# APPS.net
KiCad netlist of a schematic drawn in Altium Designer
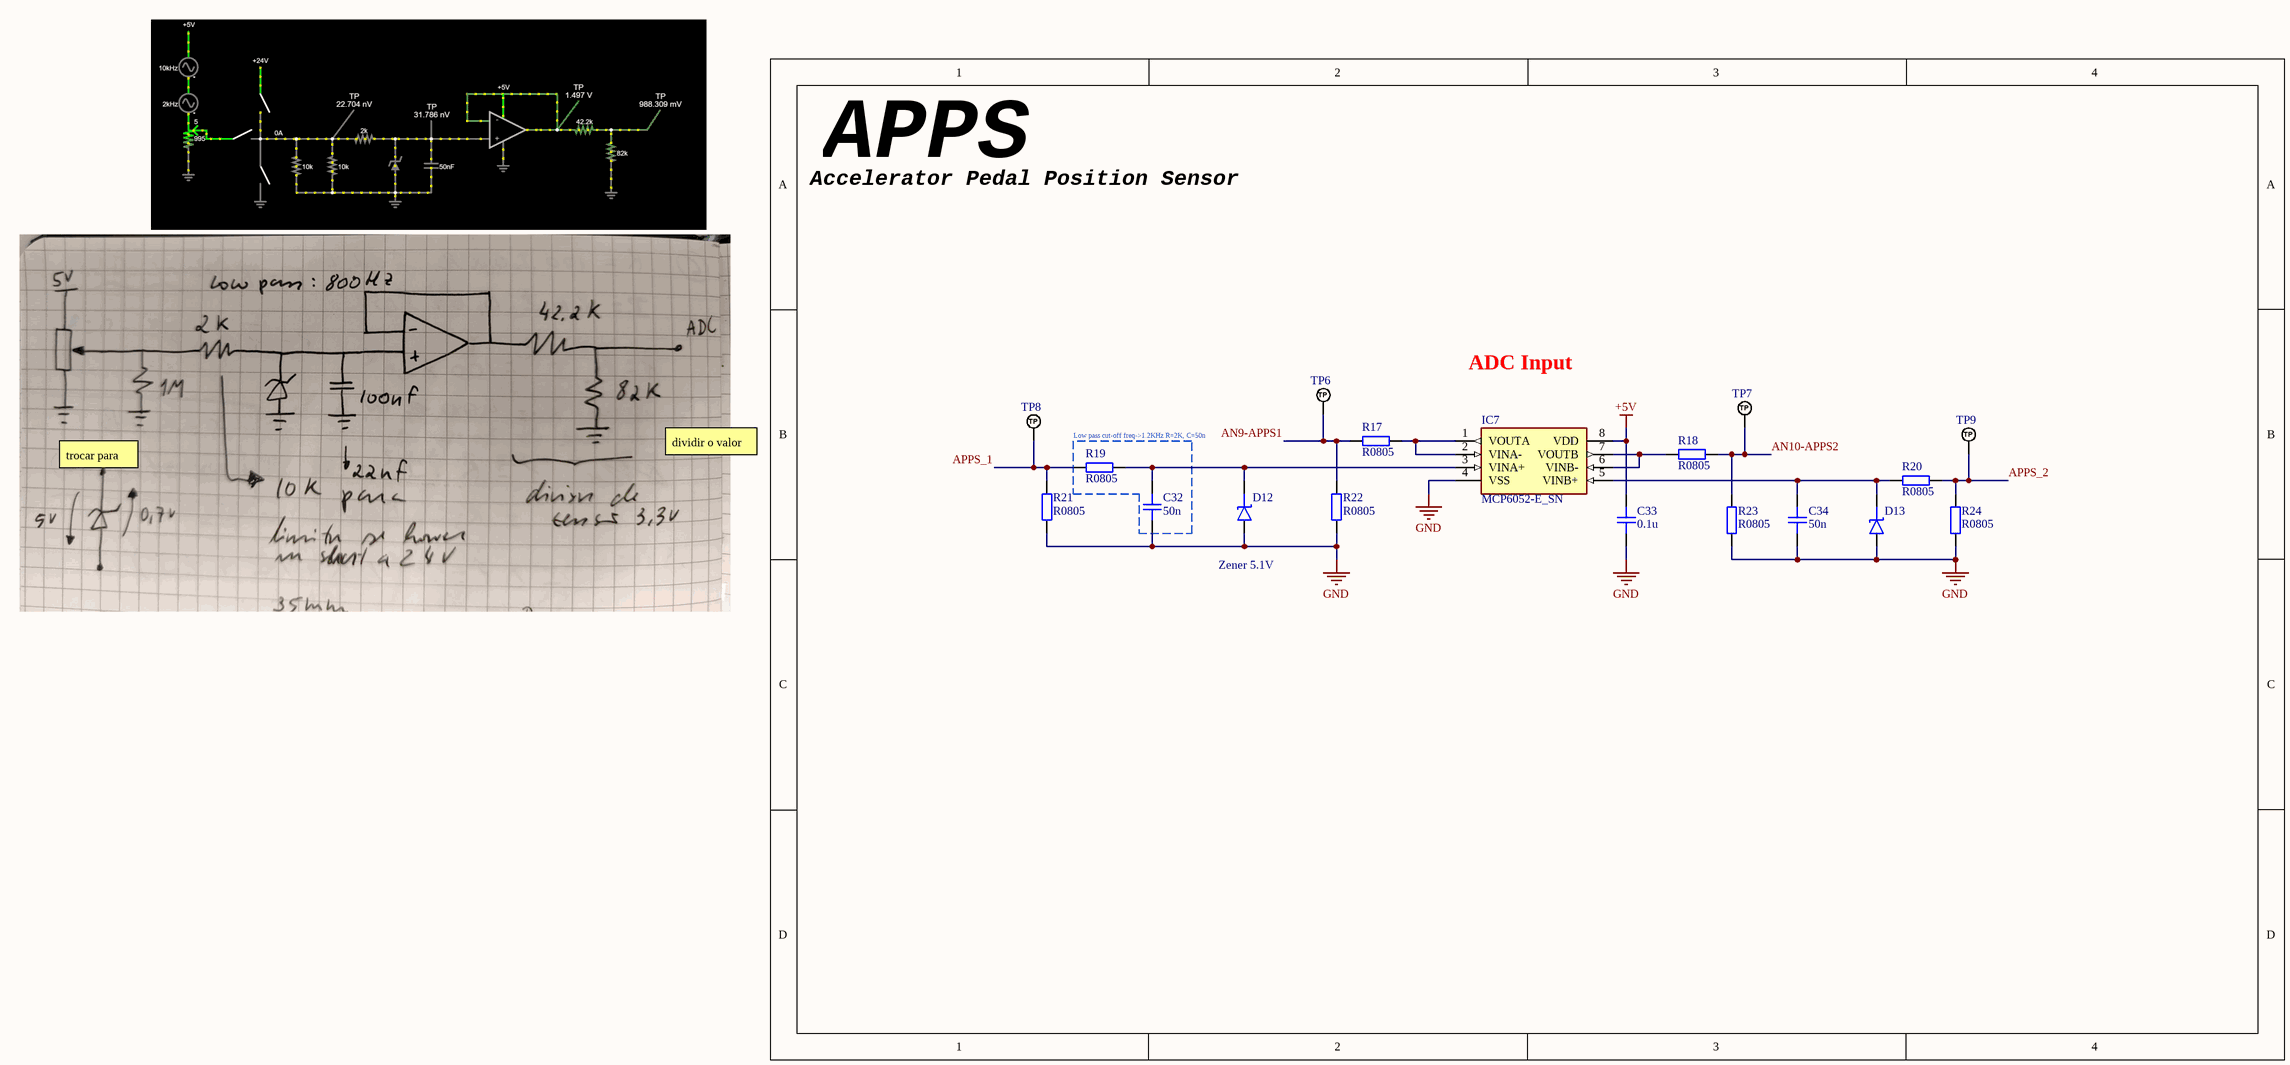
[diagram p0: APPS.SchDoc]

(export (version "E")
  (design (tool "Eeschema 10.0.6"))
  (components
    (comp (ref "C32")
      (value "50n")
      (footprint "CAP_0805")
      (description "Capacitor SMD 0805 10V")
      (libsource (lib "Schematic-Lib-PhilsLab") (part "CAP_0805_10V"))
    )
    (comp (ref "C33")
      (value "0.1u")
      (footprint "CAP_0805")
      (description "Capacitor SMD 0805 10V")
      (libsource (lib "Schematic-Lib-PhilsLab") (part "CAP_0805_10V"))
    )
    (comp (ref "C34")
      (value "50n")
      (footprint "CAP_0805")
      (description "Capacitor SMD 0805 10V")
      (libsource (lib "Schematic-Lib-PhilsLab") (part "CAP_0805_10V"))
    )
    (comp (ref "D12")
      (value "D_SCHOTTKY_SOD_323")
      (footprint "SOD-323")
      (description "Diode Schottky SMD SOD-323")
      (libsource (lib "PhilsLab") (part "D_SCHOTTKY_SOD_323"))
    )
    (comp (ref "D13")
      (value "D_SCHOTTKY_SOD_323")
      (footprint "SOD-323")
      (description "Diode Schottky SMD SOD-323")
      (libsource (lib "PhilsLab") (part "D_SCHOTTKY_SOD_323"))
    )
    (comp (ref "IC7")
      (value "MCP6052-E_SN")
      (footprint "Pedro_pcb_lib:SOIC127P600X175-8N")
      (description "Integrated Circuit")
      (fields
        (field (name "MANUFACTURER_PART_NUMBER") "MCP6052-E/SN")
        (field (name "MOUSER PART NUMBER") "579-MCP6052-E/SN")
      )
      (libsource (lib "*") (part "MCP6052-E_SN"))
    )
    (comp (ref "R17")
      (value "R0805")
      (footprint "RES_0805")
      (description "Resistor SMD 0805")
      (libsource (lib "Schematic-Lib-PhilsLab") (part "RES_0805"))
    )
    (comp (ref "R18")
      (value "R0805")
      (footprint "RES_0805")
      (description "Resistor SMD 0805")
      (libsource (lib "Schematic-Lib-PhilsLab") (part "RES_0805"))
    )
    (comp (ref "R19")
      (value "R0805")
      (footprint "RES_0805")
      (description "Resistor SMD 0805")
      (libsource (lib "Schematic-Lib-PhilsLab") (part "RES_0805"))
    )
    (comp (ref "R20")
      (value "R0805")
      (footprint "RES_0805")
      (description "Resistor SMD 0805")
      (libsource (lib "Schematic-Lib-PhilsLab") (part "RES_0805"))
    )
    (comp (ref "R21")
      (value "R0805")
      (footprint "RES_0805")
      (description "Resistor SMD 0805")
      (libsource (lib "Schematic-Lib-PhilsLab") (part "RES_0805"))
    )
    (comp (ref "R22")
      (value "R0805")
      (footprint "RES_0805")
      (description "Resistor SMD 0805")
      (libsource (lib "Schematic-Lib-PhilsLab") (part "RES_0805"))
    )
    (comp (ref "R23")
      (value "R0805")
      (footprint "RES_0805")
      (description "Resistor SMD 0805")
      (libsource (lib "Schematic-Lib-PhilsLab") (part "RES_0805"))
    )
    (comp (ref "R24")
      (value "R0805")
      (footprint "RES_0805")
      (description "Resistor SMD 0805")
      (libsource (lib "Schematic-Lib-PhilsLab") (part "RES_0805"))
    )
    (comp (ref "TP6")
      (value "TP_NOBOM")
      (footprint "PAD_RND_1MM")
      (description "Test Point Round 1mm (NO BOM)")
      (libsource (lib "Schematic-Lib-PhilsLab") (part "TEST_POINT_RND_1MM"))
    )
    (comp (ref "TP7")
      (value "TP_NOBOM")
      (footprint "PAD_RND_1MM")
      (description "Test Point Round 1mm (NO BOM)")
      (libsource (lib "Schematic-Lib-PhilsLab") (part "TEST_POINT_RND_1MM"))
    )
    (comp (ref "TP8")
      (value "TP_NOBOM")
      (footprint "PAD_RND_1MM")
      (description "Test Point Round 1mm (NO BOM)")
      (libsource (lib "Schematic-Lib-PhilsLab") (part "TEST_POINT_RND_1MM"))
    )
    (comp (ref "TP9")
      (value "TP_NOBOM")
      (footprint "PAD_RND_1MM")
      (description "Test Point Round 1mm (NO BOM)")
      (libsource (lib "Schematic-Lib-PhilsLab") (part "TEST_POINT_RND_1MM"))
    )
  )
  (nets
    (net (code "1") (name "+5V") (class "Default")
      (node (ref "C33") (pin "2") (pinfunction "2_2") (pintype "passive"))
      (node (ref "IC7") (pin "8") (pinfunction "VDD_8") (pintype "power_in"))
    )
    (net (code "2") (name "/AN9-APPS1") (class "Default")
      (node (ref "R17") (pin "2") (pinfunction "2_2") (pintype "passive"))
      (node (ref "R22") (pin "1") (pinfunction "1_1") (pintype "passive"))
      (node (ref "TP6") (pin "1") (pinfunction "TP_1") (pintype "passive"))
    )
    (net (code "3") (name "/AN10-APPS2") (class "Default")
      (node (ref "R18") (pin "1") (pinfunction "1_1") (pintype "passive"))
      (node (ref "R23") (pin "1") (pinfunction "1_1") (pintype "passive"))
      (node (ref "TP7") (pin "1") (pinfunction "TP_1") (pintype "passive"))
    )
    (net (code "4") (name "/APPS_1") (class "Default")
      (node (ref "R19") (pin "1") (pinfunction "1_1") (pintype "passive"))
      (node (ref "R21") (pin "2") (pinfunction "2_2") (pintype "passive"))
      (node (ref "TP8") (pin "1") (pinfunction "TP_1") (pintype "passive"))
    )
    (net (code "5") (name "/APPS_2") (class "Default")
      (node (ref "R20") (pin "2") (pinfunction "2_2") (pintype "passive"))
      (node (ref "R24") (pin "2") (pinfunction "2_2") (pintype "passive"))
      (node (ref "TP9") (pin "1") (pinfunction "TP_1") (pintype "passive"))
    )
    (net (code "6") (name "GND") (class "Default")
      (node (ref "C32") (pin "2") (pinfunction "2_2") (pintype "passive"))
      (node (ref "C33") (pin "1") (pinfunction "1_1") (pintype "passive"))
      (node (ref "C34") (pin "2") (pinfunction "2_2") (pintype "passive"))
      (node (ref "D12") (pin "A") (pinfunction "A_A") (pintype "passive"))
      (node (ref "D13") (pin "A") (pinfunction "A_A") (pintype "passive"))
      (node (ref "IC7") (pin "4") (pinfunction "VSS_4") (pintype "power_in"))
      (node (ref "R21") (pin "1") (pinfunction "1_1") (pintype "passive"))
      (node (ref "R22") (pin "2") (pinfunction "2_2") (pintype "passive"))
      (node (ref "R23") (pin "2") (pinfunction "2_2") (pintype "passive"))
      (node (ref "R24") (pin "1") (pinfunction "1_1") (pintype "passive"))
    )
    (net (code "7") (name "Net-(IC7-VINA+)") (class "Default")
      (node (ref "C32") (pin "1") (pinfunction "1_1") (pintype "passive"))
      (node (ref "D12") (pin "K") (pinfunction "K_K") (pintype "passive"))
      (node (ref "IC7") (pin "3") (pinfunction "VINA+_3") (pintype "input"))
      (node (ref "R19") (pin "2") (pinfunction "2_2") (pintype "passive"))
    )
    (net (code "8") (name "Net-(IC7-VINA-)") (class "Default")
      (node (ref "IC7") (pin "1") (pinfunction "VOUTA_1") (pintype "output"))
      (node (ref "IC7") (pin "2") (pinfunction "VINA-_2") (pintype "input"))
      (node (ref "R17") (pin "1") (pinfunction "1_1") (pintype "passive"))
    )
    (net (code "9") (name "Net-(IC7-VINB+)") (class "Default")
      (node (ref "C34") (pin "1") (pinfunction "1_1") (pintype "passive"))
      (node (ref "D13") (pin "K") (pinfunction "K_K") (pintype "passive"))
      (node (ref "IC7") (pin "5") (pinfunction "VINB+_5") (pintype "input"))
      (node (ref "R20") (pin "1") (pinfunction "1_1") (pintype "passive"))
    )
    (net (code "10") (name "Net-(IC7-VINB-)") (class "Default")
      (node (ref "IC7") (pin "6") (pinfunction "VINB-_6") (pintype "input"))
      (node (ref "IC7") (pin "7") (pinfunction "VOUTB_7") (pintype "output"))
      (node (ref "R18") (pin "2") (pinfunction "2_2") (pintype "passive"))
    )
  )
)
